# STM32_DDS.net
KiCad netlist of a schematic drawn in Altium Designer
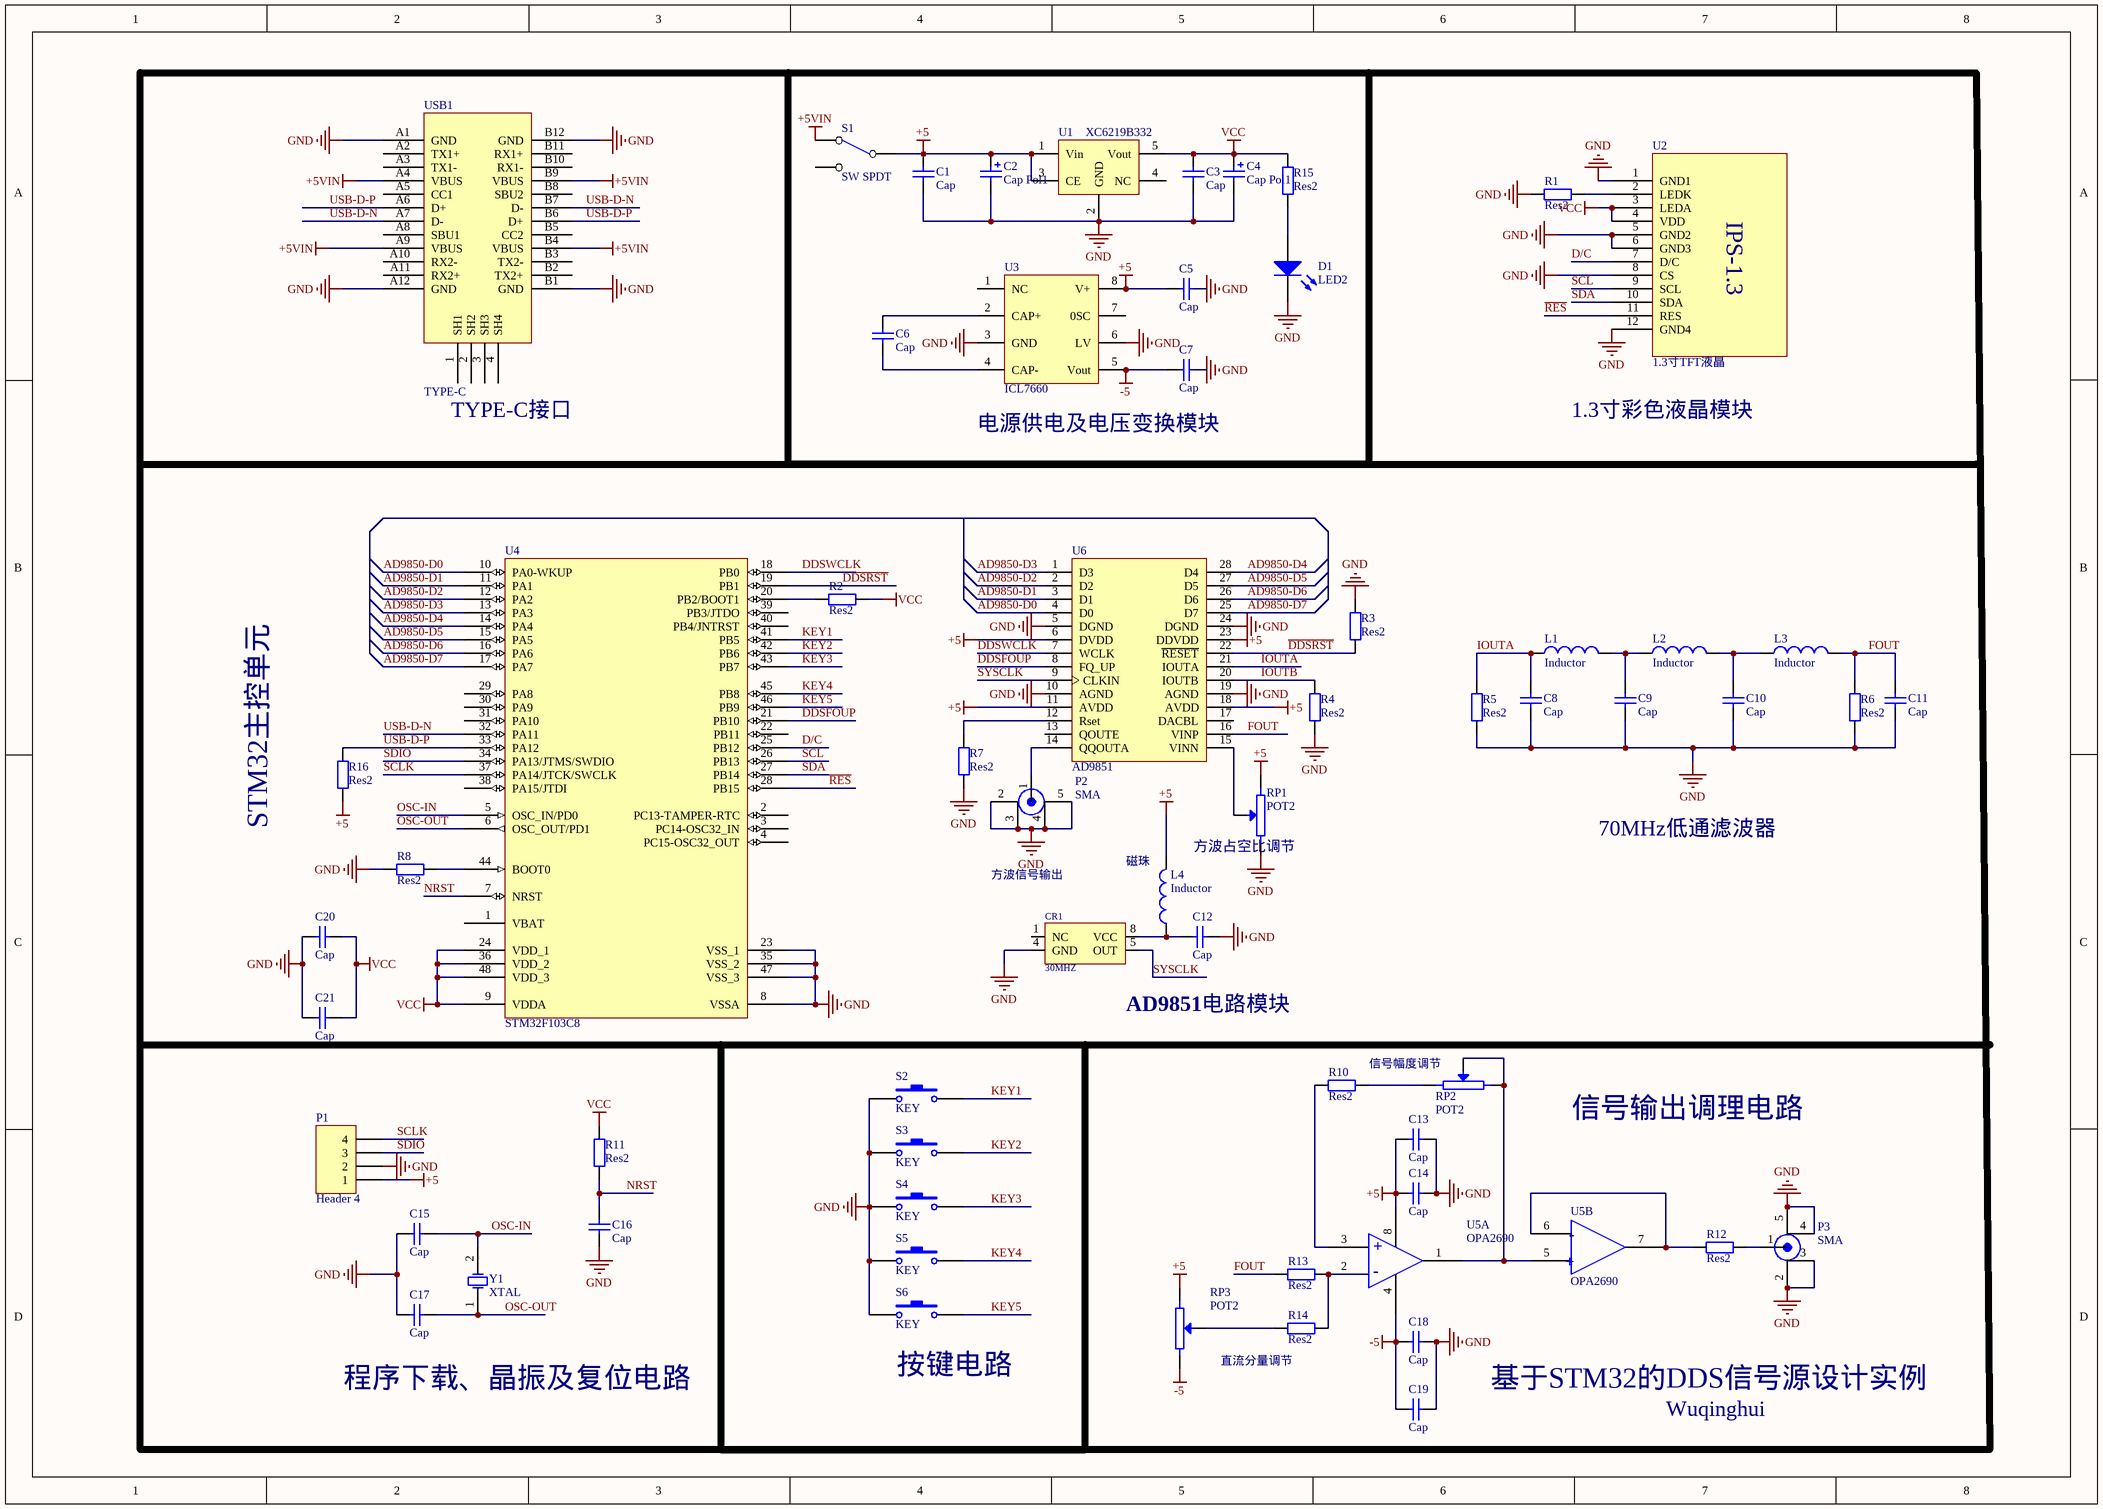
[diagram p0: 基于STM32的DDS信号源的设计实例.SchDoc]

(export (version "E")
  (design (tool "Eeschema 10.0.6"))
  (components
    (comp (ref "C1")
      (value "Cap")
      (footprint "C0805")
      (description "Capacitor")
      (fields (field (name "PUBLISHER") "Altium Limited"))
      (libsource (lib "基于STM32的DDS信号源设计实例") (part "Cap"))
    )
    (comp (ref "C2")
      (value "Cap Pol1")
      (footprint "C1210_N")
      (description "Polarized Capacitor (Radial)")
      (fields (field (name "PUBLISHER") "Altium Limited"))
      (libsource (lib "基于STM32的DDS信号源设计实例") (part "Cap Pol1"))
    )
    (comp (ref "C3")
      (value "Cap")
      (footprint "C0805")
      (description "Capacitor")
      (fields (field (name "PUBLISHER") "Altium Limited"))
      (libsource (lib "基于STM32的DDS信号源设计实例") (part "Cap"))
    )
    (comp (ref "C4")
      (value "Cap Pol1")
      (footprint "C1210_N")
      (description "Polarized Capacitor (Radial)")
      (fields (field (name "PUBLISHER") "Altium Limited"))
      (libsource (lib "基于STM32的DDS信号源设计实例") (part "Cap Pol1"))
    )
    (comp (ref "C5")
      (value "Cap")
      (footprint "C0805")
      (description "Capacitor")
      (fields (field (name "PUBLISHER") "Altium Limited"))
      (libsource (lib "基于STM32的DDS信号源设计实例") (part "Cap"))
    )
    (comp (ref "C6")
      (value "Cap")
      (footprint "C0805")
      (description "Capacitor")
      (fields (field (name "PUBLISHER") "Altium Limited"))
      (libsource (lib "基于STM32的DDS信号源设计实例") (part "Cap"))
    )
    (comp (ref "C7")
      (value "Cap")
      (footprint "C0805")
      (description "Capacitor")
      (fields (field (name "PUBLISHER") "Altium Limited"))
      (libsource (lib "基于STM32的DDS信号源设计实例") (part "Cap"))
    )
    (comp (ref "C8")
      (value "Cap")
      (footprint "C0805")
      (description "Capacitor")
      (fields (field (name "PUBLISHER") "Altium Limited"))
      (libsource (lib "基于STM32的DDS信号源设计实例") (part "Cap"))
    )
    (comp (ref "C9")
      (value "Cap")
      (footprint "C0805")
      (description "Capacitor")
      (fields (field (name "PUBLISHER") "Altium Limited"))
      (libsource (lib "基于STM32的DDS信号源设计实例") (part "Cap"))
    )
    (comp (ref "C10")
      (value "Cap")
      (footprint "C0805")
      (description "Capacitor")
      (fields (field (name "PUBLISHER") "Altium Limited"))
      (libsource (lib "基于STM32的DDS信号源设计实例") (part "Cap"))
    )
    (comp (ref "C11")
      (value "Cap")
      (footprint "C0805")
      (description "Capacitor")
      (fields (field (name "PUBLISHER") "Altium Limited"))
      (libsource (lib "基于STM32的DDS信号源设计实例") (part "Cap"))
    )
    (comp (ref "C12")
      (value "Cap")
      (footprint "C0805")
      (description "Capacitor")
      (fields (field (name "PUBLISHER") "Altium Limited"))
      (libsource (lib "基于STM32的DDS信号源设计实例") (part "Cap"))
    )
    (comp (ref "C13")
      (value "Cap")
      (footprint "C0805")
      (description "Capacitor")
      (fields (field (name "PUBLISHER") "Altium Limited"))
      (libsource (lib "基于STM32的DDS信号源设计实例") (part "Cap"))
    )
    (comp (ref "C14")
      (value "Cap")
      (footprint "C0805")
      (description "Capacitor")
      (fields (field (name "PUBLISHER") "Altium Limited"))
      (libsource (lib "基于STM32的DDS信号源设计实例") (part "Cap"))
    )
    (comp (ref "C15")
      (value "Cap")
      (footprint "C0805")
      (description "Capacitor")
      (fields (field (name "PUBLISHER") "Altium Limited"))
      (libsource (lib "基于STM32的DDS信号源设计实例") (part "Cap"))
    )
    (comp (ref "C16")
      (value "Cap")
      (footprint "C0805")
      (description "Capacitor")
      (fields (field (name "PUBLISHER") "Altium Limited"))
      (libsource (lib "基于STM32的DDS信号源设计实例") (part "Cap"))
    )
    (comp (ref "C17")
      (value "Cap")
      (footprint "C0805")
      (description "Capacitor")
      (fields (field (name "PUBLISHER") "Altium Limited"))
      (libsource (lib "基于STM32的DDS信号源设计实例") (part "Cap"))
    )
    (comp (ref "C18")
      (value "Cap")
      (footprint "C0805")
      (description "Capacitor")
      (fields (field (name "PUBLISHER") "Altium Limited"))
      (libsource (lib "基于STM32的DDS信号源设计实例") (part "Cap"))
    )
    (comp (ref "C19")
      (value "Cap")
      (footprint "C0805")
      (description "Capacitor")
      (fields (field (name "PUBLISHER") "Altium Limited"))
      (libsource (lib "基于STM32的DDS信号源设计实例") (part "Cap"))
    )
    (comp (ref "C20")
      (value "Cap")
      (footprint "C0805")
      (description "Capacitor")
      (fields (field (name "PUBLISHER") "Altium Limited"))
      (libsource (lib "基于STM32的DDS信号源设计实例") (part "Cap"))
    )
    (comp (ref "C21")
      (value "Cap")
      (footprint "C0805")
      (description "Capacitor")
      (fields (field (name "PUBLISHER") "Altium Limited"))
      (libsource (lib "基于STM32的DDS信号源设计实例") (part "Cap"))
    )
    (comp (ref "CR1")
      (value "30MHZ")
      (footprint "CRYSTAL-SMT-5X7")
      (libsource (lib "基于STM32的DDS信号源设计实例") (part "CRYSTAL-DIP8"))
    )
    (comp (ref "D1")
      (value "LED2")
      (footprint "D0805+")
      (description "Typical RED, GREEN, YELLOW, AMBER GaAs LED")
      (fields (field (name "PUBLISHER") "Altium Limited"))
      (libsource (lib "基于STM32的DDS信号源设计实例") (part "LED2"))
    )
    (comp (ref "L1")
      (value "Inductor")
      (footprint "6-0805_N")
      (fields (field (name "PUBLISHER") "Altium Limited"))
      (libsource (lib "基于STM32的DDS信号源设计实例") (part "Inductor"))
    )
    (comp (ref "L2")
      (value "Inductor")
      (footprint "6-0805_N")
      (fields (field (name "PUBLISHER") "Altium Limited"))
      (libsource (lib "基于STM32的DDS信号源设计实例") (part "Inductor"))
    )
    (comp (ref "L3")
      (value "Inductor")
      (footprint "6-0805_N")
      (fields (field (name "PUBLISHER") "Altium Limited"))
      (libsource (lib "基于STM32的DDS信号源设计实例") (part "Inductor"))
    )
    (comp (ref "L4")
      (value "Inductor")
      (footprint "6-0805_N")
      (fields (field (name "PUBLISHER") "Altium Limited"))
      (libsource (lib "基于STM32的DDS信号源设计实例") (part "Inductor"))
    )
    (comp (ref "P1")
      (value "Header 4")
      (footprint "HDR1X4")
      (description "Header, 4-Pin")
      (fields (field (name "PUBLISHER") "Altium Limited"))
      (libsource (lib "基于STM32的DDS信号源设计实例") (part "Header 4"))
    )
    (comp (ref "P2") (value "SMA") (footprint "SMA-KE") (libsource (lib "Schlib1") (part "SMA")))
    (comp (ref "P3") (value "SMA") (footprint "SMA-KE") (libsource (lib "原理图库") (part "SMA")))
    (comp (ref "R1")
      (value "Res2")
      (footprint "6-0805_N")
      (description "Resistor")
      (fields (field (name "PUBLISHER") "Altium Limited"))
      (libsource (lib "基于STM32的DDS信号源设计实例") (part "Res2"))
    )
    (comp (ref "R2")
      (value "Res2")
      (footprint "6-0805_N")
      (description "Resistor")
      (fields (field (name "PUBLISHER") "Altium Limited"))
      (libsource (lib "基于STM32的DDS信号源设计实例") (part "Res2"))
    )
    (comp (ref "R3")
      (value "Res2")
      (footprint "6-0805_N")
      (description "Resistor")
      (fields (field (name "PUBLISHER") "Altium Limited"))
      (libsource (lib "") (part "Res2_1"))
    )
    (comp (ref "R4")
      (value "Res2")
      (footprint "6-0805_N")
      (description "Resistor")
      (fields (field (name "PUBLISHER") "Altium Limited"))
      (libsource (lib "") (part "Res2_1"))
    )
    (comp (ref "R5")
      (value "Res2")
      (footprint "6-0805_N")
      (description "Resistor")
      (fields (field (name "PUBLISHER") "Altium Limited"))
      (libsource (lib "") (part "Res2_1"))
    )
    (comp (ref "R6")
      (value "Res2")
      (footprint "6-0805_N")
      (description "Resistor")
      (fields (field (name "PUBLISHER") "Altium Limited"))
      (libsource (lib "") (part "Res2_1"))
    )
    (comp (ref "R7")
      (value "Res2")
      (footprint "6-0805_N")
      (description "Resistor")
      (fields (field (name "PUBLISHER") "Altium Limited"))
      (libsource (lib "") (part "Res2_1"))
    )
    (comp (ref "R8")
      (value "Res2")
      (footprint "6-0805_N")
      (description "Resistor")
      (fields (field (name "PUBLISHER") "Altium Limited"))
      (libsource (lib "") (part "Res2_2"))
    )
    (comp (ref "R10")
      (value "Res2")
      (footprint "6-0805_N")
      (description "Resistor")
      (fields (field (name "PUBLISHER") "Altium Limited"))
      (libsource (lib "基于STM32的DDS信号源设计实例") (part "Res2"))
    )
    (comp (ref "R11")
      (value "Res2")
      (footprint "6-0805_N")
      (description "Resistor")
      (fields (field (name "PUBLISHER") "Altium Limited"))
      (libsource (lib "") (part "Res2_1"))
    )
    (comp (ref "R12")
      (value "Res2")
      (footprint "6-0805_N")
      (description "Resistor")
      (fields (field (name "PUBLISHER") "Altium Limited"))
      (libsource (lib "基于STM32的DDS信号源设计实例") (part "Res2"))
    )
    (comp (ref "R13")
      (value "Res2")
      (footprint "6-0805_N")
      (description "Resistor")
      (fields (field (name "PUBLISHER") "Altium Limited"))
      (libsource (lib "基于STM32的DDS信号源设计实例") (part "Res2"))
    )
    (comp (ref "R14")
      (value "Res2")
      (footprint "6-0805_N")
      (description "Resistor")
      (fields (field (name "PUBLISHER") "Altium Limited"))
      (libsource (lib "基于STM32的DDS信号源设计实例") (part "Res2"))
    )
    (comp (ref "R15")
      (value "Res2")
      (footprint "6-0805_N")
      (description "Resistor")
      (fields (field (name "PUBLISHER") "Altium Limited"))
      (libsource (lib "") (part "Res2_1"))
    )
    (comp (ref "R16")
      (value "Res2")
      (footprint "6-0805_N")
      (description "Resistor")
      (fields (field (name "PUBLISHER") "Altium Limited"))
      (libsource (lib "") (part "Res2_1"))
    )
    (comp (ref "RP1")
      (value "POT2")
      (footprint "VR7")
      (description "Potentiometer")
      (libsource (lib "基于STM32的DDS信号源设计实例") (part "POT2"))
    )
    (comp (ref "RP2")
      (value "POT2")
      (footprint "VR7")
      (description "Potentiometer")
      (libsource (lib "基于STM32的DDS信号源设计实例") (part "POT2"))
    )
    (comp (ref "RP3")
      (value "POT2")
      (footprint "VR7")
      (description "Potentiometer")
      (libsource (lib "基于STM32的DDS信号源设计实例") (part "POT2"))
    )
    (comp (ref "S1")
      (value "SW SPDT")
      (footprint "SW")
      (libsource (lib "基于STM32的DDS信号源设计实例") (part "SW SPDT"))
    )
    (comp (ref "S2")
      (value "KEY")
      (footprint "SW-MINI")
      (description "Switch")
      (fields (field (name "PUBLISHER") "Altium Limited"))
      (libsource (lib "基于STM32的DDS信号源设计实例") (part "SW-PB"))
    )
    (comp (ref "S3")
      (value "KEY")
      (footprint "SW-MINI")
      (description "Switch")
      (fields (field (name "PUBLISHER") "Altium Limited"))
      (libsource (lib "基于STM32的DDS信号源设计实例") (part "SW-PB"))
    )
    (comp (ref "S4")
      (value "KEY")
      (footprint "SW-MINI")
      (description "Switch")
      (fields (field (name "PUBLISHER") "Altium Limited"))
      (libsource (lib "基于STM32的DDS信号源设计实例") (part "SW-PB"))
    )
    (comp (ref "S5")
      (value "KEY")
      (footprint "SW-MINI")
      (description "Switch")
      (fields (field (name "PUBLISHER") "Altium Limited"))
      (libsource (lib "基于STM32的DDS信号源设计实例") (part "SW-PB"))
    )
    (comp (ref "S6")
      (value "KEY")
      (footprint "SW-MINI")
      (description "Switch")
      (fields (field (name "PUBLISHER") "Altium Limited"))
      (libsource (lib "基于STM32的DDS信号源设计实例") (part "SW-PB"))
    )
    (comp (ref "U1")
      (value "XC6219B332")
      (footprint "SOT23-5L")
      (libsource (lib "基于STM32的DDS信号源设计实例") (part "XC6219"))
    )
    (comp (ref "U2")
      (value "1.3寸TFT液晶")
      (footprint "1.3-TFT-TPS")
      (libsource (lib "基于STM32的DDS信号源设计实例") (part "1.3寸TFT液晶"))
    )
    (comp (ref "U3")
      (value "ICL7660")
      (footprint "SO8_N")
      (libsource (lib "基于STM32的DDS信号源设计实例") (part "ICL7660"))
    )
    (comp (ref "U4")
      (value "STM32F103C8")
      (footprint "TQFP-48")
      (description "Flaah:64/RAM:20/IO:36")
      (fields (field (name "版权归属") "源创客"))
      (libsource (lib "基于STM32的DDS信号源设计实例") (part "STM32F103C8"))
    )
    (comp (ref "U5") (value "OPA2690") (footprint "SO-8") (libsource (lib "原理图库") (part "OPA2690")))
    (comp (ref "U6") (value "AD9851") (footprint "TSSOP28") (libsource (lib "原理图库") (part "AD9851")))
    (comp (ref "USB1")
      (value "TYPE-C")
      (footprint "TYPE-C")
      (libsource (lib "基于STM32的DDS信号源设计实例") (part "TYPE-C"))
    )
    (comp (ref "Y1")
      (value "XTAL")
      (footprint "XTAL2")
      (description "Crystal Oscillator")
      (fields (field (name "PUBLISHER") "Altium Limited"))
      (libsource (lib "基于STM32的DDS信号源设计实例") (part "XTAL"))
    )
  )
  (nets
    (net (code "1") (name "+5") (class "Default")
      (node (ref "C1") (pin "2") (pinfunction "2_2") (pintype "passive"))
      (node (ref "C13") (pin "1") (pinfunction "1_1") (pintype "passive"))
      (node (ref "C14") (pin "1") (pinfunction "1_1") (pintype "passive"))
      (node (ref "C2") (pin "1") (pinfunction "1_1") (pintype "passive"))
      (node (ref "C5") (pin "1") (pinfunction "1_1") (pintype "passive"))
      (node (ref "L4") (pin "2") (pinfunction "2_2") (pintype "passive"))
      (node (ref "P1") (pin "1") (pinfunction "1_1") (pintype "passive"))
      (node (ref "R16") (pin "1") (pinfunction "1_1") (pintype "passive"))
      (node (ref "RP1") (pin "2") (pinfunction "2_2") (pintype "passive"))
      (node (ref "RP3") (pin "1") (pinfunction "1_1") (pintype "passive"))
      (node (ref "S1") (pin "2") (pinfunction "COMMON_2") (pintype "passive"))
      (node (ref "U1") (pin "1") (pinfunction "Vin_1") (pintype "passive"))
      (node (ref "U1") (pin "3") (pinfunction "CE_3") (pintype "passive"))
      (node (ref "U3") (pin "8") (pinfunction "V+_8") (pintype "passive"))
      (node (ref "U5") (pin "8") (pintype "passive"))
      (node (ref "U6") (pin "11") (pinfunction "AVDD_11") (pintype "passive"))
      (node (ref "U6") (pin "18") (pinfunction "AVDD_18") (pintype "passive"))
      (node (ref "U6") (pin "23") (pinfunction "DDVDD_23") (pintype "passive"))
      (node (ref "U6") (pin "6") (pinfunction "DVDD_6") (pintype "passive"))
    )
    (net (code "2") (name "+5VIN") (class "Default")
      (node (ref "S1") (pin "1") (pinfunction "NC_1") (pintype "passive"))
      (node (ref "USB1") (pin "A4") (pinfunction "VBUS_A4") (pintype "passive"))
      (node (ref "USB1") (pin "A9") (pinfunction "VBUS_A9") (pintype "passive"))
      (node (ref "USB1") (pin "B4") (pinfunction "VBUS_B4") (pintype "passive"))
      (node (ref "USB1") (pin "B9") (pinfunction "VBUS_B9") (pintype "passive"))
    )
    (net (code "3") (name "-5") (class "Default")
      (node (ref "C18") (pin "1") (pinfunction "1_1") (pintype "passive"))
      (node (ref "C19") (pin "1") (pinfunction "1_1") (pintype "passive"))
      (node (ref "C7") (pin "1") (pinfunction "1_1") (pintype "passive"))
      (node (ref "RP3") (pin "2") (pinfunction "2_2") (pintype "passive"))
      (node (ref "U3") (pin "5") (pinfunction "Vout_5") (pintype "passive"))
      (node (ref "U5") (pin "4") (pintype "passive"))
    )
    (net (code "4") (name "/AD9850-D0") (class "Default")
      (node (ref "U4") (pin "10") (pinfunction "PA0-WKUP_10") (pintype "bidirectional"))
      (node (ref "U6") (pin "4") (pinfunction "D0_4") (pintype "passive"))
    )
    (net (code "5") (name "/AD9850-D1") (class "Default")
      (node (ref "U4") (pin "11") (pinfunction "PA1_11") (pintype "bidirectional"))
      (node (ref "U6") (pin "3") (pinfunction "D1_3") (pintype "passive"))
    )
    (net (code "6") (name "/AD9850-D2") (class "Default")
      (node (ref "U4") (pin "12") (pinfunction "PA2_12") (pintype "bidirectional"))
      (node (ref "U6") (pin "2") (pinfunction "D2_2") (pintype "passive"))
    )
    (net (code "7") (name "/AD9850-D3") (class "Default")
      (node (ref "U4") (pin "13") (pinfunction "PA3_13") (pintype "bidirectional"))
      (node (ref "U6") (pin "1") (pinfunction "D3_1") (pintype "passive"))
    )
    (net (code "8") (name "/AD9850-D4") (class "Default")
      (node (ref "U4") (pin "14") (pinfunction "PA4_14") (pintype "bidirectional"))
      (node (ref "U6") (pin "28") (pinfunction "D4_28") (pintype "passive"))
    )
    (net (code "9") (name "/AD9850-D5") (class "Default")
      (node (ref "U4") (pin "15") (pinfunction "PA5_15") (pintype "bidirectional"))
      (node (ref "U6") (pin "27") (pinfunction "D5_27") (pintype "passive"))
    )
    (net (code "10") (name "/AD9850-D6") (class "Default")
      (node (ref "U4") (pin "16") (pinfunction "PA6_16") (pintype "bidirectional"))
      (node (ref "U6") (pin "26") (pinfunction "D6_26") (pintype "passive"))
    )
    (net (code "11") (name "/AD9850-D7") (class "Default")
      (node (ref "U4") (pin "17") (pinfunction "PA7_17") (pintype "bidirectional"))
      (node (ref "U6") (pin "25") (pinfunction "D7_25") (pintype "passive"))
    )
    (net (code "12") (name "/DDSFOUP") (class "Default")
      (node (ref "U4") (pin "21") (pinfunction "PB10_21") (pintype "bidirectional"))
      (node (ref "U6") (pin "8") (pinfunction "FQ_UP_8") (pintype "passive"))
    )
    (net (code "13") (name "/DDSWCLK") (class "Default")
      (node (ref "U4") (pin "18") (pinfunction "PB0_18") (pintype "bidirectional"))
      (node (ref "U6") (pin "7") (pinfunction "WCLK_7") (pintype "passive"))
    )
    (net (code "14") (name "/D{slash}C") (class "Default")
      (node (ref "U2") (pin "7") (pinfunction "D/C_7") (pintype "passive"))
      (node (ref "U4") (pin "25") (pinfunction "PB12_25") (pintype "bidirectional"))
    )
    (net (code "15") (name "/FOUT") (class "Default")
      (node (ref "C11") (pin "2") (pinfunction "2_2") (pintype "passive"))
      (node (ref "L3") (pin "2") (pinfunction "2_2") (pintype "passive"))
      (node (ref "R13") (pin "1") (pinfunction "1_1") (pintype "passive"))
      (node (ref "R6") (pin "2") (pinfunction "2_2") (pintype "passive"))
      (node (ref "U6") (pin "16") (pinfunction "VINP_16") (pintype "passive"))
    )
    (net (code "16") (name "/IOUTA") (class "Default")
      (node (ref "C8") (pin "2") (pinfunction "2_2") (pintype "passive"))
      (node (ref "L1") (pin "1") (pinfunction "1_1") (pintype "passive"))
      (node (ref "R5") (pin "2") (pinfunction "2_2") (pintype "passive"))
      (node (ref "U6") (pin "21") (pinfunction "IOUTA_21") (pintype "passive"))
    )
    (net (code "17") (name "/IOUTB") (class "Default")
      (node (ref "R4") (pin "2") (pinfunction "2_2") (pintype "passive"))
      (node (ref "U6") (pin "20") (pinfunction "IOUTB_20") (pintype "passive"))
    )
    (net (code "18") (name "/KEY1") (class "Default")
      (node (ref "S2") (pin "2") (pinfunction "2_2") (pintype "passive"))
      (node (ref "U4") (pin "41") (pinfunction "PB5_41") (pintype "bidirectional"))
    )
    (net (code "19") (name "/KEY2") (class "Default")
      (node (ref "S3") (pin "2") (pinfunction "2_2") (pintype "passive"))
      (node (ref "U4") (pin "42") (pinfunction "PB6_42") (pintype "bidirectional"))
    )
    (net (code "20") (name "/KEY3") (class "Default")
      (node (ref "S4") (pin "2") (pinfunction "2_2") (pintype "passive"))
      (node (ref "U4") (pin "43") (pinfunction "PB7_43") (pintype "bidirectional"))
    )
    (net (code "21") (name "/KEY4") (class "Default")
      (node (ref "S5") (pin "2") (pinfunction "2_2") (pintype "passive"))
      (node (ref "U4") (pin "45") (pinfunction "PB8_45") (pintype "bidirectional"))
    )
    (net (code "22") (name "/KEY5") (class "Default")
      (node (ref "S6") (pin "2") (pinfunction "2_2") (pintype "passive"))
      (node (ref "U4") (pin "46") (pinfunction "PB9_46") (pintype "bidirectional"))
    )
    (net (code "23") (name "/NRST") (class "Default")
      (node (ref "C16") (pin "2") (pinfunction "2_2") (pintype "passive"))
      (node (ref "R11") (pin "1") (pinfunction "1_1") (pintype "passive"))
      (node (ref "U4") (pin "7") (pinfunction "NRST_7") (pintype "bidirectional"))
    )
    (net (code "24") (name "/OSC-IN") (class "Default")
      (node (ref "C15") (pin "2") (pinfunction "2_2") (pintype "passive"))
      (node (ref "U4") (pin "5") (pinfunction "OSC_IN/PD0_5") (pintype "input"))
      (node (ref "Y1") (pin "2") (pinfunction "OSC2_2") (pintype "passive"))
    )
    (net (code "25") (name "/OSC-OUT") (class "Default")
      (node (ref "C17") (pin "2") (pinfunction "2_2") (pintype "passive"))
      (node (ref "U4") (pin "6") (pinfunction "OSC_OUT/PD1_6") (pintype "output"))
      (node (ref "Y1") (pin "1") (pinfunction "OSC1_1") (pintype "passive"))
    )
    (net (code "26") (name "/SCL") (class "Default")
      (node (ref "U2") (pin "9") (pinfunction "SCL_9") (pintype "passive"))
      (node (ref "U4") (pin "26") (pinfunction "PB13_26") (pintype "bidirectional"))
    )
    (net (code "27") (name "/SCLK") (class "Default")
      (node (ref "P1") (pin "4") (pinfunction "4_4") (pintype "passive"))
      (node (ref "U4") (pin "37") (pinfunction "PA14/JTCK/SWCLK_37") (pintype "bidirectional"))
    )
    (net (code "28") (name "/SDA") (class "Default")
      (node (ref "U2") (pin "10") (pinfunction "SDA_10") (pintype "passive"))
      (node (ref "U4") (pin "27") (pinfunction "PB14_27") (pintype "bidirectional"))
    )
    (net (code "29") (name "/SDIO") (class "Default")
      (node (ref "P1") (pin "3") (pinfunction "3_3") (pintype "passive"))
      (node (ref "U4") (pin "34") (pinfunction "PA13/JTMS/SWDIO_34") (pintype "bidirectional"))
    )
    (net (code "30") (name "/SYSCLK") (class "Default")
      (node (ref "CR1") (pin "5") (pinfunction "OUT_5") (pintype "passive"))
      (node (ref "U6") (pin "9") (pinfunction "CLKIN_9") (pintype "passive"))
    )
    (net (code "31") (name "/USB-D-N") (class "Default")
      (node (ref "U4") (pin "32") (pinfunction "PA11_32") (pintype "bidirectional"))
      (node (ref "USB1") (pin "A7") (pinfunction "D-_A7") (pintype "passive"))
      (node (ref "USB1") (pin "B7") (pinfunction "D-_B7") (pintype "passive"))
    )
    (net (code "32") (name "/USB-D-P") (class "Default")
      (node (ref "R16") (pin "2") (pinfunction "2_2") (pintype "passive"))
      (node (ref "U4") (pin "33") (pinfunction "PA12_33") (pintype "bidirectional"))
      (node (ref "USB1") (pin "A6") (pinfunction "D+_A6") (pintype "passive"))
      (node (ref "USB1") (pin "B6") (pinfunction "D+_B6") (pintype "passive"))
    )
    (net (code "33") (name "/~{DDSRST}") (class "Default")
      (node (ref "R3") (pin "1") (pinfunction "1_1") (pintype "passive"))
      (node (ref "U4") (pin "19") (pinfunction "PB1_19") (pintype "bidirectional"))
      (node (ref "U6") (pin "22") (pinfunction "~{RESET}_22") (pintype "passive"))
    )
    (net (code "34") (name "/~{RES}") (class "Default")
      (node (ref "U2") (pin "11") (pinfunction "RES_11") (pintype "passive"))
      (node (ref "U4") (pin "28") (pinfunction "PB15_28") (pintype "bidirectional"))
    )
    (net (code "35") (name "GND") (class "Default")
      (node (ref "C1") (pin "1") (pinfunction "1_1") (pintype "passive"))
      (node (ref "C10") (pin "1") (pinfunction "1_1") (pintype "passive"))
      (node (ref "C11") (pin "1") (pinfunction "1_1") (pintype "passive"))
      (node (ref "C12") (pin "2") (pinfunction "2_2") (pintype "passive"))
      (node (ref "C13") (pin "2") (pinfunction "2_2") (pintype "passive"))
      (node (ref "C14") (pin "2") (pinfunction "2_2") (pintype "passive"))
      (node (ref "C15") (pin "1") (pinfunction "1_1") (pintype "passive"))
      (node (ref "C16") (pin "1") (pinfunction "1_1") (pintype "passive"))
      (node (ref "C17") (pin "1") (pinfunction "1_1") (pintype "passive"))
      (node (ref "C18") (pin "2") (pinfunction "2_2") (pintype "passive"))
      (node (ref "C19") (pin "2") (pinfunction "2_2") (pintype "passive"))
      (node (ref "C2") (pin "2") (pinfunction "2_2") (pintype "passive"))
      (node (ref "C20") (pin "1") (pinfunction "1_1") (pintype "passive"))
      (node (ref "C21") (pin "1") (pinfunction "1_1") (pintype "passive"))
      (node (ref "C3") (pin "1") (pinfunction "1_1") (pintype "passive"))
      (node (ref "C4") (pin "2") (pinfunction "2_2") (pintype "passive"))
      (node (ref "C5") (pin "2") (pinfunction "2_2") (pintype "passive"))
      (node (ref "C7") (pin "2") (pinfunction "2_2") (pintype "passive"))
      (node (ref "C8") (pin "1") (pinfunction "1_1") (pintype "passive"))
      (node (ref "C9") (pin "1") (pinfunction "1_1") (pintype "passive"))
      (node (ref "CR1") (pin "4") (pinfunction "GND_4") (pintype "passive"))
      (node (ref "D1") (pin "K") (pinfunction "K_K") (pintype "passive"))
      (node (ref "P1") (pin "2") (pinfunction "2_2") (pintype "passive"))
      (node (ref "P2") (pin "2") (pintype "passive"))
      (node (ref "P2") (pin "3") (pintype "passive"))
      (node (ref "P2") (pin "4") (pintype "passive"))
      (node (ref "P2") (pin "5") (pintype "passive"))
      (node (ref "P3") (pin "2") (pintype "passive"))
      (node (ref "P3") (pin "3") (pintype "passive"))
      (node (ref "P3") (pin "4") (pintype "passive"))
      (node (ref "P3") (pin "5") (pintype "passive"))
      (node (ref "R1") (pin "1") (pinfunction "1_1") (pintype "passive"))
      (node (ref "R3") (pin "2") (pinfunction "2_2") (pintype "passive"))
      (node (ref "R4") (pin "1") (pinfunction "1_1") (pintype "passive"))
      (node (ref "R5") (pin "1") (pinfunction "1_1") (pintype "passive"))
      (node (ref "R6") (pin "1") (pinfunction "1_1") (pintype "passive"))
      (node (ref "R7") (pin "1") (pinfunction "1_1") (pintype "passive"))
      (node (ref "R8") (pin "2") (pinfunction "2_2") (pintype "passive"))
      (node (ref "RP1") (pin "1") (pinfunction "1_1") (pintype "passive"))
      (node (ref "S2") (pin "1") (pinfunction "1_1") (pintype "passive"))
      (node (ref "S3") (pin "1") (pinfunction "1_1") (pintype "passive"))
      (node (ref "S4") (pin "1") (pinfunction "1_1") (pintype "passive"))
      (node (ref "S5") (pin "1") (pinfunction "1_1") (pintype "passive"))
      (node (ref "S6") (pin "1") (pinfunction "1_1") (pintype "passive"))
      (node (ref "U1") (pin "2") (pinfunction "GND_2") (pintype "power_in"))
      (node (ref "U2") (pin "1") (pinfunction "GND1_1") (pintype "passive"))
      (node (ref "U2") (pin "12") (pinfunction "GND4_12") (pintype "passive"))
      (node (ref "U2") (pin "5") (pinfunction "GND2_5") (pintype "passive"))
      (node (ref "U2") (pin "6") (pinfunction "GND3_6") (pintype "passive"))
      (node (ref "U2") (pin "8") (pinfunction "CS_8") (pintype "passive"))
      (node (ref "U3") (pin "3") (pinfunction "GND_3") (pintype "passive"))
      (node (ref "U3") (pin "6") (pinfunction "LV_6") (pintype "passive"))
      (node (ref "U4") (pin "23") (pinfunction "VSS_1_23") (pintype "power_in"))
      (node (ref "U4") (pin "35") (pinfunction "VSS_2_35") (pintype "power_in"))
      (node (ref "U4") (pin "47") (pinfunction "VSS_3_47") (pintype "power_in"))
      (node (ref "U4") (pin "8") (pinfunction "VSSA_8") (pintype "power_in"))
      (node (ref "U6") (pin "10") (pinfunction "AGND_10") (pintype "passive"))
      (node (ref "U6") (pin "19") (pinfunction "AGND_19") (pintype "passive"))
      (node (ref "U6") (pin "24") (pinfunction "DGND_24") (pintype "passive"))
      (node (ref "U6") (pin "5") (pinfunction "DGND_5") (pintype "passive"))
      (node (ref "USB1") (pin "A1") (pinfunction "GND_A1") (pintype "passive"))
      (node (ref "USB1") (pin "A12") (pinfunction "GND_A12") (pintype "passive"))
      (node (ref "USB1") (pin "B1") (pinfunction "GND_B1") (pintype "passive"))
      (node (ref "USB1") (pin "B12") (pinfunction "GND_B12") (pintype "passive"))
    )
    (net (code "36") (name "Net-(C9-Pad2)") (class "Default")
      (node (ref "C9") (pin "2") (pinfunction "2_2") (pintype "passive"))
      (node (ref "L1") (pin "2") (pinfunction "2_2") (pintype "passive"))
      (node (ref "L2") (pin "1") (pinfunction "1_1") (pintype "passive"))
    )
    (net (code "37") (name "Net-(C10-Pad2)") (class "Default")
      (node (ref "C10") (pin "2") (pinfunction "2_2") (pintype "passive"))
      (node (ref "L2") (pin "2") (pinfunction "2_2") (pintype "passive"))
      (node (ref "L3") (pin "1") (pinfunction "1_1") (pintype "passive"))
    )
    (net (code "38") (name "Net-(CR1-VCC)") (class "Default")
      (node (ref "C12") (pin "1") (pinfunction "1_1") (pintype "passive"))
      (node (ref "CR1") (pin "8") (pinfunction "VCC_8") (pintype "passive"))
      (node (ref "L4") (pin "1") (pinfunction "1_1") (pintype "passive"))
    )
    (net (code "39") (name "Net-(D1-PadA)") (class "Default")
      (node (ref "D1") (pin "A") (pinfunction "A_A") (pintype "passive"))
      (node (ref "R15") (pin "1") (pinfunction "1_1") (pintype "passive"))
    )
    (net (code "40") (name "Net-(P3-Pad1)") (class "Default")
      (node (ref "P3") (pin "1") (pintype "passive"))
      (node (ref "R12") (pin "2") (pinfunction "2_2") (pintype "passive"))
    )
    (net (code "41") (name "Net-(R10-Pad2)") (class "Default")
      (node (ref "R10") (pin "2") (pinfunction "2_2") (pintype "passive"))
      (node (ref "RP2") (pin "1") (pinfunction "1_1") (pintype "passive"))
    )
    (net (code "42") (name "Net-(R12-Pad1)") (class "Default")
      (node (ref "R12") (pin "1") (pinfunction "1_1") (pintype "passive"))
      (node (ref "U5") (pin "7") (pintype "passive"))
    )
    (net (code "43") (name "Net-(R13-Pad2)") (class "Default")
      (node (ref "R13") (pin "2") (pinfunction "2_2") (pintype "passive"))
      (node (ref "R14") (pin "2") (pinfunction "2_2") (pintype "passive"))
      (node (ref "U5") (pin "2") (pintype "passive"))
    )
    (net (code "44") (name "Net-(R14-Pad1)") (class "Default")
      (node (ref "R14") (pin "1") (pinfunction "1_1") (pintype "passive"))
      (node (ref "RP3") (pin "3") (pinfunction "3_3") (pintype "passive"))
    )
    (net (code "45") (name "Net-(RP2-Pad2)") (class "Default")
      (node (ref "RP2") (pin "2") (pinfunction "2_2") (pintype "passive"))
      (node (ref "RP2") (pin "3") (pinfunction "3_3") (pintype "passive"))
      (node (ref "U5") (pin "1") (pintype "passive"))
    )
    (net (code "46") (name "Net-(U2-LEDK)") (class "Default")
      (node (ref "R1") (pin "2") (pinfunction "2_2") (pintype "passive"))
      (node (ref "U2") (pin "2") (pinfunction "LEDK_2") (pintype "passive"))
    )
    (net (code "47") (name "Net-(U3-CAP+)") (class "Default")
      (node (ref "C6") (pin "2") (pinfunction "2_2") (pintype "passive"))
      (node (ref "U3") (pin "2") (pinfunction "CAP+_2") (pintype "passive"))
    )
    (net (code "48") (name "Net-(U3-CAP-)") (class "Default")
      (node (ref "C6") (pin "1") (pinfunction "1_1") (pintype "passive"))
      (node (ref "U3") (pin "4") (pinfunction "CAP-_4") (pintype "passive"))
    )
    (net (code "49") (name "Net-(U4-BOOT0)") (class "Default")
      (node (ref "R8") (pin "1") (pinfunction "1_1") (pintype "passive"))
      (node (ref "U4") (pin "44") (pinfunction "BOOT0_44") (pintype "input"))
    )
    (net (code "50") (name "Net-(U4-PB2{slash}BOOT1)") (class "Default")
      (node (ref "R2") (pin "1") (pinfunction "1_1") (pintype "passive"))
      (node (ref "U4") (pin "20") (pinfunction "PB2/BOOT1_20") (pintype "bidirectional"))
    )
    (net (code "51") (name "Net-(U6-QQOUTA)") (class "Default")
      (node (ref "P2") (pin "1") (pintype "passive"))
      (node (ref "U6") (pin "14") (pinfunction "QQOUTA_14") (pintype "passive"))
    )
    (net (code "52") (name "Net-(U6-Rset)") (class "Default")
      (node (ref "R7") (pin "2") (pinfunction "2_2") (pintype "passive"))
      (node (ref "U6") (pin "12") (pinfunction "Rset_12") (pintype "passive"))
    )
    (net (code "53") (name "Net-(U6-VINN)") (class "Default")
      (node (ref "RP1") (pin "3") (pinfunction "3_3") (pintype "passive"))
      (node (ref "U6") (pin "15") (pinfunction "VINN_15") (pintype "passive"))
    )
    (net (code "54") (name "VCC") (class "Default")
      (node (ref "C20") (pin "2") (pinfunction "2_2") (pintype "passive"))
      (node (ref "C21") (pin "2") (pinfunction "2_2") (pintype "passive"))
      (node (ref "C3") (pin "2") (pinfunction "2_2") (pintype "passive"))
      (node (ref "C4") (pin "1") (pinfunction "1_1") (pintype "passive"))
      (node (ref "R11") (pin "2") (pinfunction "2_2") (pintype "passive"))
      (node (ref "R15") (pin "2") (pinfunction "2_2") (pintype "passive"))
      (node (ref "R2") (pin "2") (pinfunction "2_2") (pintype "passive"))
      (node (ref "U1") (pin "5") (pinfunction "Vout_5") (pintype "passive"))
      (node (ref "U2") (pin "3") (pinfunction "LEDA_3") (pintype "passive"))
      (node (ref "U2") (pin "4") (pinfunction "VDD_4") (pintype "passive"))
      (node (ref "U4") (pin "24") (pinfunction "VDD_1_24") (pintype "power_in"))
      (node (ref "U4") (pin "36") (pinfunction "VDD_2_36") (pintype "power_in"))
      (node (ref "U4") (pin "48") (pinfunction "VDD_3_48") (pintype "power_in"))
      (node (ref "U4") (pin "9") (pinfunction "VDDA_9") (pintype "power_in"))
    )
    (net (code "55") (name "unconnected-(CR1-NC-Pad1)") (class "Default")
      (node (ref "CR1") (pin "1") (pinfunction "NC_1") (pintype "passive"))
    )
    (net (code "56") (name "unconnected-(R10-Pad1)") (class "Default")
      (node (ref "R10") (pin "1") (pinfunction "1_1") (pintype "passive"))
    )
    (net (code "57") (name "unconnected-(S1-NO-Pad3)") (class "Default")
      (node (ref "S1") (pin "3") (pinfunction "NO_3") (pintype "passive"))
    )
    (net (code "58") (name "unconnected-(U1-NC-Pad4)") (class "Default")
      (node (ref "U1") (pin "4") (pinfunction "NC_4") (pintype "passive"))
    )
    (net (code "59") (name "unconnected-(U3-0SC-Pad7)") (class "Default")
      (node (ref "U3") (pin "7") (pinfunction "0SC_7") (pintype "passive"))
    )
    (net (code "60") (name "unconnected-(U3-NC-Pad1)") (class "Default")
      (node (ref "U3") (pin "1") (pinfunction "NC_1") (pintype "passive"))
    )
    (net (code "61") (name "unconnected-(U4-PA8-Pad29)") (class "Default")
      (node (ref "U4") (pin "29") (pinfunction "PA8_29") (pintype "bidirectional"))
    )
    (net (code "62") (name "unconnected-(U4-PA9-Pad30)") (class "Default")
      (node (ref "U4") (pin "30") (pinfunction "PA9_30") (pintype "bidirectional"))
    )
    (net (code "63") (name "unconnected-(U4-PA10-Pad31)") (class "Default")
      (node (ref "U4") (pin "31") (pinfunction "PA10_31") (pintype "bidirectional"))
    )
    (net (code "64") (name "unconnected-(U4-PA15{slash}JTDI-Pad38)") (class "Default")
      (node (ref "U4") (pin "38") (pinfunction "PA15/JTDI_38") (pintype "bidirectional"))
    )
    (net (code "65") (name "unconnected-(U4-PB3{slash}JTDO-Pad39)") (class "Default")
      (node (ref "U4") (pin "39") (pinfunction "PB3/JTDO_39") (pintype "bidirectional"))
    )
    (net (code "66") (name "unconnected-(U4-PB4{slash}JNTRST-Pad40)") (class "Default")
      (node (ref "U4") (pin "40") (pinfunction "PB4/JNTRST_40") (pintype "bidirectional"))
    )
    (net (code "67") (name "unconnected-(U4-PB11-Pad22)") (class "Default")
      (node (ref "U4") (pin "22") (pinfunction "PB11_22") (pintype "bidirectional"))
    )
    (net (code "68") (name "unconnected-(U4-PC13-TAMPER-RTC-Pad2)") (class "Default")
      (node (ref "U4") (pin "2") (pinfunction "PC13-TAMPER-RTC_2") (pintype "bidirectional"))
    )
    (net (code "69") (name "unconnected-(U4-PC14-OSC32_IN-Pad3)") (class "Default")
      (node (ref "U4") (pin "3") (pinfunction "PC14-OSC32_IN_3") (pintype "bidirectional"))
    )
    (net (code "70") (name "unconnected-(U4-PC15-OSC32_OUT-Pad4)") (class "Default")
      (node (ref "U4") (pin "4") (pinfunction "PC15-OSC32_OUT_4") (pintype "bidirectional"))
    )
    (net (code "71") (name "unconnected-(U4-VBAT-Pad1)") (class "Default")
      (node (ref "U4") (pin "1") (pinfunction "VBAT_1") (pintype "power_in"))
    )
    (net (code "72") (name "unconnected-(U5-Pad3)") (class "Default")
      (node (ref "U5") (pin "3") (pintype "passive"))
    )
    (net (code "73") (name "unconnected-(U5-Pad5)") (class "Default")
      (node (ref "U5") (pin "5") (pintype "passive"))
    )
    (net (code "74") (name "unconnected-(U5-Pad6)") (class "Default")
      (node (ref "U5") (pin "6") (pintype "passive"))
    )
    (net (code "75") (name "unconnected-(U6-DACBL-Pad17)") (class "Default")
      (node (ref "U6") (pin "17") (pinfunction "DACBL_17") (pintype "passive"))
    )
    (net (code "76") (name "unconnected-(U6-QOUTE-Pad13)") (class "Default")
      (node (ref "U6") (pin "13") (pinfunction "QOUTE_13") (pintype "passive"))
    )
    (net (code "77") (name "unconnected-(USB1-CC1-PadA5)") (class "Default")
      (node (ref "USB1") (pin "A5") (pinfunction "CC1_A5") (pintype "passive"))
    )
    (net (code "78") (name "unconnected-(USB1-CC2-PadB5)") (class "Default")
      (node (ref "USB1") (pin "B5") (pinfunction "CC2_B5") (pintype "passive"))
    )
    (net (code "79") (name "unconnected-(USB1-RX1+-PadB11)") (class "Default")
      (node (ref "USB1") (pin "B11") (pinfunction "RX1+_B11") (pintype "passive"))
    )
    (net (code "80") (name "unconnected-(USB1-RX1--PadB10)") (class "Default")
      (node (ref "USB1") (pin "B10") (pinfunction "RX1-_B10") (pintype "passive"))
    )
    (net (code "81") (name "unconnected-(USB1-RX2+-PadA11)") (class "Default")
      (node (ref "USB1") (pin "A11") (pinfunction "RX2+_A11") (pintype "passive"))
    )
    (net (code "82") (name "unconnected-(USB1-RX2--PadA10)") (class "Default")
      (node (ref "USB1") (pin "A10") (pinfunction "RX2-_A10") (pintype "passive"))
    )
    (net (code "83") (name "unconnected-(USB1-SBU1-PadA8)") (class "Default")
      (node (ref "USB1") (pin "A8") (pinfunction "SBU1_A8") (pintype "passive"))
    )
    (net (code "84") (name "unconnected-(USB1-SBU2-PadB8)") (class "Default")
      (node (ref "USB1") (pin "B8") (pinfunction "SBU2_B8") (pintype "passive"))
    )
    (net (code "85") (name "unconnected-(USB1-SH1-Pad1)") (class "Default")
      (node (ref "USB1") (pin "1") (pinfunction "SH1_1") (pintype "passive"))
    )
    (net (code "86") (name "unconnected-(USB1-SH2-Pad2)") (class "Default")
      (node (ref "USB1") (pin "2") (pinfunction "SH2_2") (pintype "passive"))
    )
    (net (code "87") (name "unconnected-(USB1-SH3-Pad3)") (class "Default")
      (node (ref "USB1") (pin "3") (pinfunction "SH3_3") (pintype "passive"))
    )
    (net (code "88") (name "unconnected-(USB1-SH4-Pad4)") (class "Default")
      (node (ref "USB1") (pin "4") (pinfunction "SH4_4") (pintype "passive"))
    )
    (net (code "89") (name "unconnected-(USB1-TX1+-PadA2)") (class "Default")
      (node (ref "USB1") (pin "A2") (pinfunction "TX1+_A2") (pintype "passive"))
    )
    (net (code "90") (name "unconnected-(USB1-TX1--PadA3)") (class "Default")
      (node (ref "USB1") (pin "A3") (pinfunction "TX1-_A3") (pintype "passive"))
    )
    (net (code "91") (name "unconnected-(USB1-TX2+-PadB2)") (class "Default")
      (node (ref "USB1") (pin "B2") (pinfunction "TX2+_B2") (pintype "passive"))
    )
    (net (code "92") (name "unconnected-(USB1-TX2--PadB3)") (class "Default")
      (node (ref "USB1") (pin "B3") (pinfunction "TX2-_B3") (pintype "passive"))
    )
  )
)
